# GWC-MCU-002-A_-_Temps.net
KiCad netlist of a schematic drawn in Altium Designer
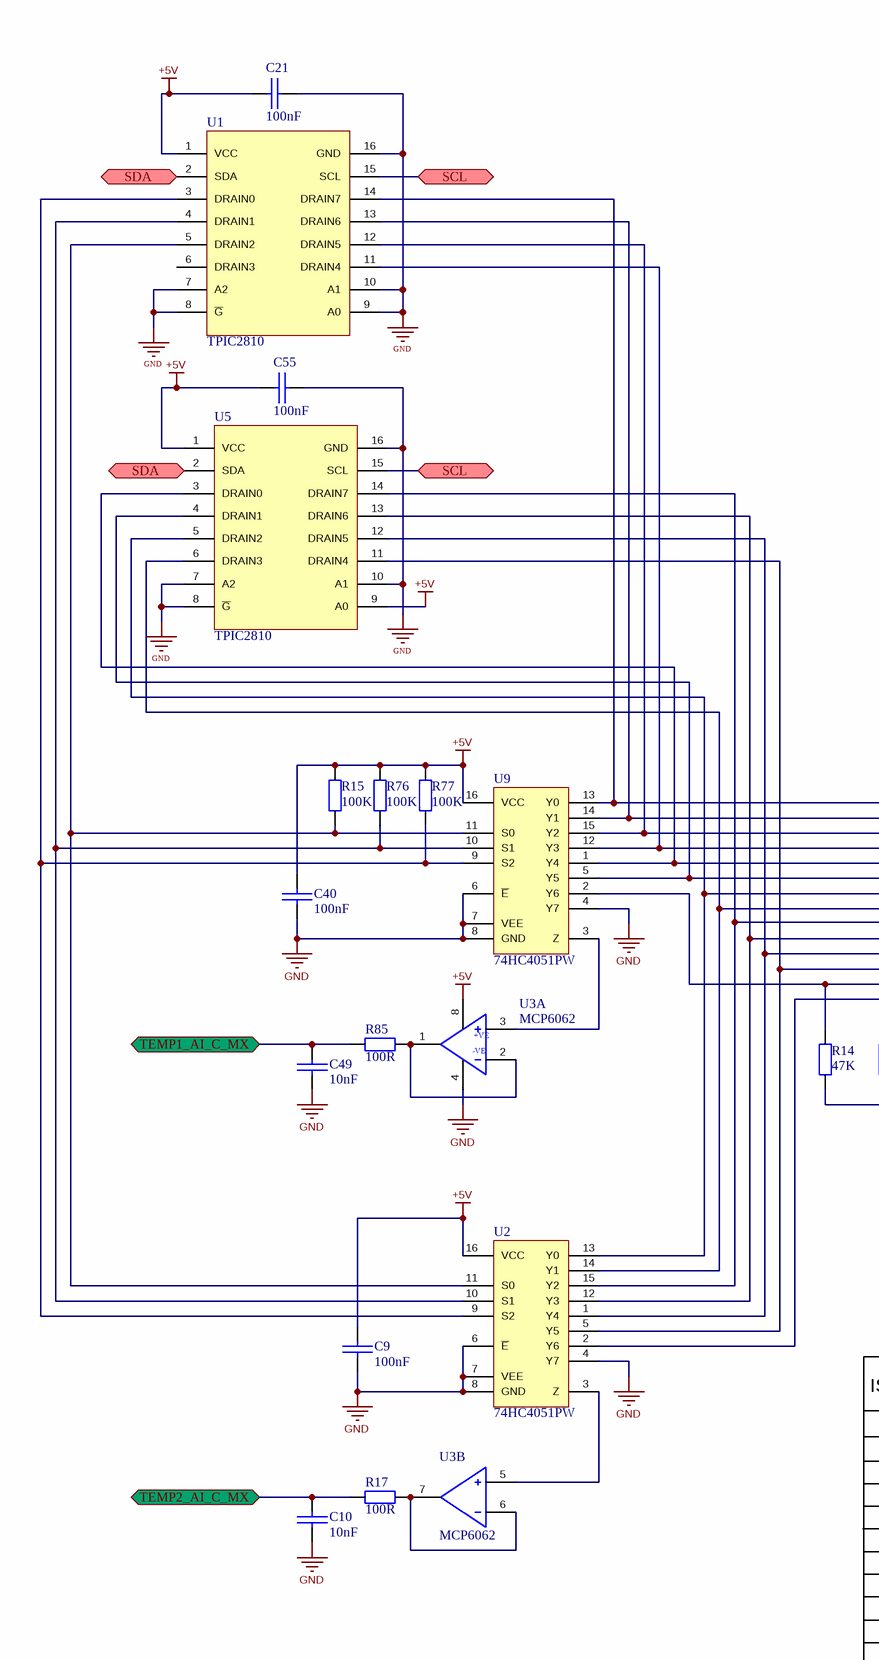
[diagram p0: GWC-MCU-002-A - Temps.SchDoc, left]
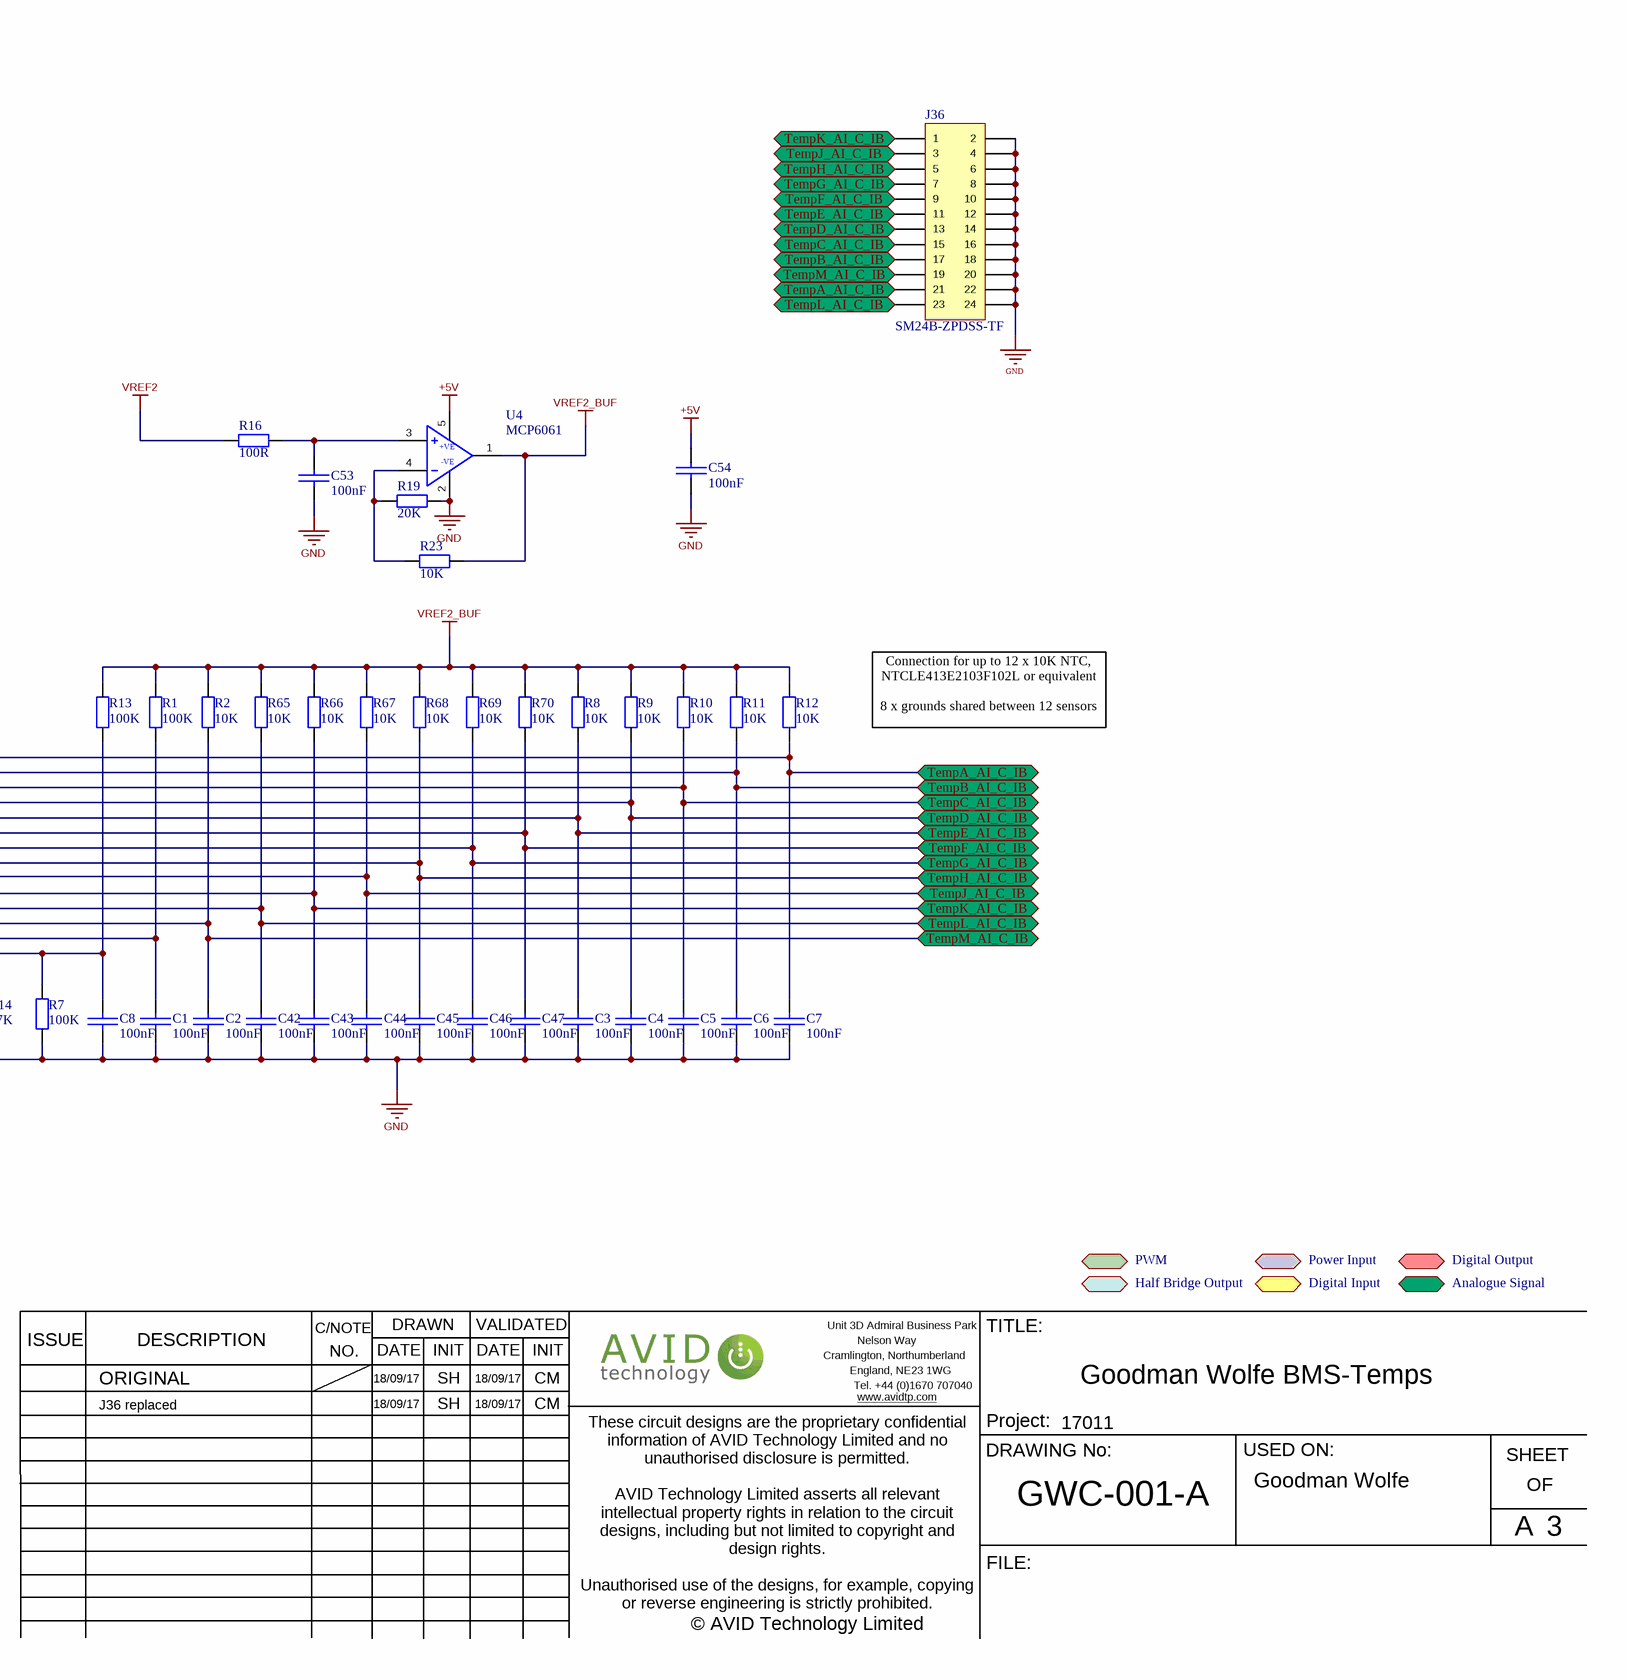
[diagram p1: GWC-MCU-002-A - Temps.SchDoc, right]

(export (version "E")
  (design (tool "Eeschema 10.0.6"))
  (components
    (comp (ref "C1")
      (value "100nF")
      (footprint "C0603")
      (description "100nF 0603 Non Polarised Capacitor")
      (fields (field (name "TOLERANCE") "10%") (field (name "MANUFACTURER") "Kemet"))
      (libsource (lib "Vayon Sch Library") (part "100nF X7R 0603"))
    )
    (comp (ref "C2")
      (value "100nF")
      (footprint "C0603")
      (description "100nF 0603 Non Polarised Capacitor")
      (fields (field (name "TOLERANCE") "10%") (field (name "MANUFACTURER") "Kemet"))
      (libsource (lib "Vayon Sch Library") (part "100nF X7R 0603"))
    )
    (comp (ref "C3")
      (value "100nF")
      (footprint "C0603")
      (description "100nF 0603 Non Polarised Capacitor")
      (fields (field (name "TOLERANCE") "10%") (field (name "MANUFACTURER") "Kemet"))
      (libsource (lib "Vayon Sch Library") (part "100nF X7R 0603"))
    )
    (comp (ref "C4")
      (value "100nF")
      (footprint "C0603")
      (description "100nF 0603 Non Polarised Capacitor")
      (fields (field (name "TOLERANCE") "10%") (field (name "MANUFACTURER") "Kemet"))
      (libsource (lib "Vayon Sch Library") (part "100nF X7R 0603"))
    )
    (comp (ref "C5")
      (value "100nF")
      (footprint "C0603")
      (description "100nF 0603 Non Polarised Capacitor")
      (fields (field (name "TOLERANCE") "10%") (field (name "MANUFACTURER") "Kemet"))
      (libsource (lib "Vayon Sch Library") (part "100nF X7R 0603"))
    )
    (comp (ref "C6")
      (value "100nF")
      (footprint "C0603")
      (description "100nF 0603 Non Polarised Capacitor")
      (fields (field (name "TOLERANCE") "10%") (field (name "MANUFACTURER") "Kemet"))
      (libsource (lib "Vayon Sch Library") (part "100nF X7R 0603"))
    )
    (comp (ref "C7")
      (value "100nF")
      (footprint "C0603")
      (description "100nF 0603 Non Polarised Capacitor")
      (fields (field (name "TOLERANCE") "10%") (field (name "MANUFACTURER") "Kemet"))
      (libsource (lib "Vayon Sch Library") (part "100nF X7R 0603"))
    )
    (comp (ref "C8")
      (value "100nF")
      (footprint "C0603")
      (description "100nF 0603 Non Polarised Capacitor")
      (fields (field (name "TOLERANCE") "10%") (field (name "MANUFACTURER") "Kemet"))
      (libsource (lib "Vayon Sch Library") (part "100nF X7R 0603"))
    )
    (comp (ref "C9")
      (value "100nF")
      (footprint "C0603")
      (description "100nF 0603 Non Polarised Capacitor")
      (fields (field (name "TOLERANCE") "10%") (field (name "MANUFACTURER") "Kemet"))
      (libsource (lib "Vayon Sch Library") (part "100nF X7R 0603"))
    )
    (comp (ref "C10")
      (value "10nF")
      (footprint "0603")
      (description "10nF Non Polarised Capacitor")
      (fields (field (name "TOLERANCE") "10%") (field (name "MANUFACTURER") "Kemet"))
      (libsource (lib "Vayon Sch Library") (part "10nF 0603 X7R"))
    )
    (comp (ref "C21")
      (value "100nF")
      (footprint "C0603")
      (description "100nF 0603 Non Polarised Capacitor")
      (fields (field (name "TOLERANCE") "10%") (field (name "MANUFACTURER") "Kemet"))
      (libsource (lib "Vayon Sch Library") (part "100nF X7R 0603"))
    )
    (comp (ref "C40")
      (value "100nF")
      (footprint "C0603")
      (description "100nF 0603 Non Polarised Capacitor")
      (fields (field (name "TOLERANCE") "10%") (field (name "MANUFACTURER") "Kemet"))
      (libsource (lib "Vayon Sch Library") (part "100nF X7R 0603"))
    )
    (comp (ref "C42")
      (value "100nF")
      (footprint "C0603")
      (description "100nF 0603 Non Polarised Capacitor")
      (fields (field (name "TOLERANCE") "10%") (field (name "MANUFACTURER") "Kemet"))
      (libsource (lib "Vayon Sch Library") (part "100nF X7R 0603"))
    )
    (comp (ref "C43")
      (value "100nF")
      (footprint "C0603")
      (description "100nF 0603 Non Polarised Capacitor")
      (fields (field (name "TOLERANCE") "10%") (field (name "MANUFACTURER") "Kemet"))
      (libsource (lib "Vayon Sch Library") (part "100nF X7R 0603"))
    )
    (comp (ref "C44")
      (value "100nF")
      (footprint "C0603")
      (description "100nF 0603 Non Polarised Capacitor")
      (fields (field (name "TOLERANCE") "10%") (field (name "MANUFACTURER") "Kemet"))
      (libsource (lib "Vayon Sch Library") (part "100nF X7R 0603"))
    )
    (comp (ref "C45")
      (value "100nF")
      (footprint "C0603")
      (description "100nF 0603 Non Polarised Capacitor")
      (fields (field (name "TOLERANCE") "10%") (field (name "MANUFACTURER") "Kemet"))
      (libsource (lib "Vayon Sch Library") (part "100nF X7R 0603"))
    )
    (comp (ref "C46")
      (value "100nF")
      (footprint "C0603")
      (description "100nF 0603 Non Polarised Capacitor")
      (fields (field (name "TOLERANCE") "10%") (field (name "MANUFACTURER") "Kemet"))
      (libsource (lib "Vayon Sch Library") (part "100nF X7R 0603"))
    )
    (comp (ref "C47")
      (value "100nF")
      (footprint "C0603")
      (description "100nF 0603 Non Polarised Capacitor")
      (fields (field (name "TOLERANCE") "10%") (field (name "MANUFACTURER") "Kemet"))
      (libsource (lib "Vayon Sch Library") (part "100nF X7R 0603"))
    )
    (comp (ref "C49")
      (value "10nF")
      (footprint "0603")
      (description "10nF Non Polarised Capacitor")
      (fields (field (name "TOLERANCE") "10%") (field (name "MANUFACTURER") "Kemet"))
      (libsource (lib "Vayon Sch Library") (part "10nF 0603 X7R"))
    )
    (comp (ref "C53")
      (value "100nF")
      (footprint "C0603")
      (description "100nF 0603 Non Polarised Capacitor")
      (fields (field (name "TOLERANCE") "10%") (field (name "MANUFACTURER") "Kemet"))
      (libsource (lib "Vayon Sch Library") (part "100nF X7R 0603"))
    )
    (comp (ref "C54")
      (value "100nF")
      (footprint "C0603")
      (description "100nF 0603 Non Polarised Capacitor")
      (fields (field (name "TOLERANCE") "10%") (field (name "MANUFACTURER") "Kemet"))
      (libsource (lib "Vayon Sch Library") (part "100nF X7R 0603"))
    )
    (comp (ref "C55")
      (value "100nF")
      (footprint "C0603")
      (description "100nF 0603 Non Polarised Capacitor")
      (fields (field (name "TOLERANCE") "10%") (field (name "MANUFACTURER") "Kemet"))
      (libsource (lib "Vayon Sch Library") (part "100nF X7R 0603"))
    )
    (comp (ref "J36")
      (value "SM24B-ZPDSS-TF")
      (footprint "24 Way ZPD Connecctor")
      (description "Header, 24-Pin, Dual row, SM24B-ZPDSS-TF")
      (fields (field (name "PUBLISHER") "Altium Limited"))
      (libsource (lib "Miscellaneous Connectors") (part "Header 12X2"))
    )
    (comp (ref "R1")
      (value "100K")
      (footprint "0603")
      (description "100K 0603 Resistor")
      (fields (field (name "TOLERANCE") "1%") (field (name "MANUFACTURER") "Phycomp"))
      (libsource (lib "Vayon Sch Library") (part "100K 0603 Resistor"))
    )
    (comp (ref "R2")
      (value "10K")
      (footprint "0603")
      (description "10K 0603 Resistor")
      (fields (field (name "TOLERANCE") "1%") (field (name "MANUFACTURER") "Phycomp"))
      (libsource (lib "Vayon Sch Library") (part "10K 0603 Resistor"))
    )
    (comp (ref "R7")
      (value "100K")
      (footprint "0603")
      (description "100K 0603 Resistor")
      (fields (field (name "TOLERANCE") "1%") (field (name "MANUFACTURER") "Phycomp"))
      (libsource (lib "Vayon Sch Library") (part "100K 0603 Resistor"))
    )
    (comp (ref "R8")
      (value "10K")
      (footprint "0603")
      (description "10K 0603 Resistor")
      (fields (field (name "TOLERANCE") "1%") (field (name "MANUFACTURER") "Phycomp"))
      (libsource (lib "Vayon Sch Library") (part "10K 0603 Resistor"))
    )
    (comp (ref "R9")
      (value "10K")
      (footprint "0603")
      (description "10K 0603 Resistor")
      (fields (field (name "TOLERANCE") "1%") (field (name "MANUFACTURER") "Phycomp"))
      (libsource (lib "Vayon Sch Library") (part "10K 0603 Resistor"))
    )
    (comp (ref "R10")
      (value "10K")
      (footprint "0603")
      (description "10K 0603 Resistor")
      (fields (field (name "TOLERANCE") "1%") (field (name "MANUFACTURER") "Phycomp"))
      (libsource (lib "Vayon Sch Library") (part "10K 0603 Resistor"))
    )
    (comp (ref "R11")
      (value "10K")
      (footprint "0603")
      (description "10K 0603 Resistor")
      (fields (field (name "TOLERANCE") "1%") (field (name "MANUFACTURER") "Phycomp"))
      (libsource (lib "Vayon Sch Library") (part "10K 0603 Resistor"))
    )
    (comp (ref "R12")
      (value "10K")
      (footprint "0603")
      (description "10K 0603 Resistor")
      (fields (field (name "TOLERANCE") "1%") (field (name "MANUFACTURER") "Phycomp"))
      (libsource (lib "Vayon Sch Library") (part "10K 0603 Resistor"))
    )
    (comp (ref "R13")
      (value "100K")
      (footprint "0603")
      (description "100K 0603 Resistor")
      (fields (field (name "TOLERANCE") "1%") (field (name "MANUFACTURER") "Phycomp"))
      (libsource (lib "Vayon Sch Library") (part "100K 0603 Resistor"))
    )
    (comp (ref "R14")
      (value "47K")
      (footprint "0603")
      (description "47K 0603 Resistor")
      (fields (field (name "TOLERANCE") "1%") (field (name "MANUFACTURER") "Phycomp"))
      (libsource (lib "Vayon Sch Library") (part "47K 0603 Resistor"))
    )
    (comp (ref "R15")
      (value "100K")
      (footprint "0603")
      (description "100K 0603 Resistor")
      (fields (field (name "TOLERANCE") "1%") (field (name "MANUFACTURER") "Phycomp"))
      (libsource (lib "") (part "100K 0603 Resistor_1"))
    )
    (comp (ref "R16")
      (value "100R")
      (footprint "0603")
      (description "100R 0603 Resistor")
      (fields (field (name "TOLERANCE") "1%") (field (name "MANUFACTURER") "Multicomp"))
      (libsource (lib "Vayon Sch Library") (part "100R 0603 Resistor"))
    )
    (comp (ref "R17")
      (value "100R")
      (footprint "0603")
      (description "100R 0603 Resistor")
      (fields (field (name "TOLERANCE") "1%") (field (name "MANUFACTURER") "Multicomp"))
      (libsource (lib "Vayon Sch Library") (part "100R 0603 Resistor"))
    )
    (comp (ref "R19")
      (value "20K")
      (footprint "0603")
      (description "100R 0603 Resistor")
      (fields (field (name "TOLERANCE") "1%") (field (name "MANUFACTURER") "Multicomp"))
      (libsource (lib "Vayon Sch Library") (part "100R 0603 Resistor"))
    )
    (comp (ref "R23")
      (value "10K")
      (footprint "0603")
      (description "100R 0603 Resistor")
      (fields (field (name "TOLERANCE") "1%") (field (name "MANUFACTURER") "Multicomp"))
      (libsource (lib "Vayon Sch Library") (part "100R 0603 Resistor"))
    )
    (comp (ref "R65")
      (value "10K")
      (footprint "0603")
      (description "10K 0603 Resistor")
      (fields (field (name "TOLERANCE") "1%") (field (name "MANUFACTURER") "Phycomp"))
      (libsource (lib "Vayon Sch Library") (part "10K 0603 Resistor"))
    )
    (comp (ref "R66")
      (value "10K")
      (footprint "0603")
      (description "10K 0603 Resistor")
      (fields (field (name "TOLERANCE") "1%") (field (name "MANUFACTURER") "Phycomp"))
      (libsource (lib "Vayon Sch Library") (part "10K 0603 Resistor"))
    )
    (comp (ref "R67")
      (value "10K")
      (footprint "0603")
      (description "10K 0603 Resistor")
      (fields (field (name "TOLERANCE") "1%") (field (name "MANUFACTURER") "Phycomp"))
      (libsource (lib "Vayon Sch Library") (part "10K 0603 Resistor"))
    )
    (comp (ref "R68")
      (value "10K")
      (footprint "0603")
      (description "10K 0603 Resistor")
      (fields (field (name "TOLERANCE") "1%") (field (name "MANUFACTURER") "Phycomp"))
      (libsource (lib "Vayon Sch Library") (part "10K 0603 Resistor"))
    )
    (comp (ref "R69")
      (value "10K")
      (footprint "0603")
      (description "10K 0603 Resistor")
      (fields (field (name "TOLERANCE") "1%") (field (name "MANUFACTURER") "Phycomp"))
      (libsource (lib "Vayon Sch Library") (part "10K 0603 Resistor"))
    )
    (comp (ref "R70")
      (value "10K")
      (footprint "0603")
      (description "10K 0603 Resistor")
      (fields (field (name "TOLERANCE") "1%") (field (name "MANUFACTURER") "Phycomp"))
      (libsource (lib "Vayon Sch Library") (part "10K 0603 Resistor"))
    )
    (comp (ref "R76")
      (value "100K")
      (footprint "0603")
      (description "100K 0603 Resistor")
      (fields (field (name "TOLERANCE") "1%") (field (name "MANUFACTURER") "Phycomp"))
      (libsource (lib "") (part "100K 0603 Resistor_1"))
    )
    (comp (ref "R77")
      (value "100K")
      (footprint "0603")
      (description "100K 0603 Resistor")
      (fields (field (name "TOLERANCE") "1%") (field (name "MANUFACTURER") "Phycomp"))
      (libsource (lib "Vayon Sch Library") (part "100K 0603 Resistor"))
    )
    (comp (ref "R85")
      (value "100R")
      (footprint "0603")
      (description "100R 0603 Resistor")
      (fields (field (name "TOLERANCE") "1%") (field (name "MANUFACTURER") "Multicomp"))
      (libsource (lib "Vayon Sch Library") (part "100R 0603 Resistor"))
    )
    (comp (ref "U1")
      (value "TPIC2810")
      (footprint "SOIC127P600-TPIC2810")
      (description "TPIC2810D -  Led Driver, 8 Outputs, I2C, 3V-5.5V")
      (fields (field (name "MANUFACTURER") "Texas"))
      (libsource (lib "GWC-MCU-001-A") (part "TPIC2810"))
    )
    (comp (ref "U2")
      (value "74HC4051PW")
      (footprint "TSSOP-16")
      (description "8 Channel Analogue Switch")
      (fields (field (name "MANUFACTURER") "NXP") (field (name "PART NUMBER") "74HC4051PW-Q100,11"))
      (libsource (lib "Vayon Sch Library") (part "74HC4051PW"))
    )
    (comp (ref "U3")
      (value "MCP6062")
      (footprint "SO-8")
      (description "Dual Opamp")
      (fields (field (name "MANUFACTURER") "Microchip") (field (name "PART NUMBER") "MCP6062-E/SN"))
      (libsource (lib "Vayon Sch Library") (part "MCP6062"))
    )
    (comp (ref "U4")
      (value "MCP6061")
      (footprint "SOT-23-5")
      (description "Micropower CMOS Op Amp")
      (fields (field (name "MANUFACTURER") "Microchip") (field (name "PART NUMBER") "MCP6061T-E/OT"))
      (libsource (lib "Vayon Sch Library") (part "MCP6061"))
    )
    (comp (ref "U5")
      (value "TPIC2810")
      (footprint "SOIC127P600-TPIC2810")
      (description "TPIC2810D -  Led Driver, 8 Outputs, I2C, 3V-5.5V")
      (fields (field (name "MANUFACTURER") "Texas"))
      (libsource (lib "GWC-MCU-001-A") (part "TPIC2810"))
    )
    (comp (ref "U9")
      (value "74HC4051PW")
      (footprint "TSSOP-16")
      (description "8 Channel Analogue Switch")
      (fields (field (name "MANUFACTURER") "NXP") (field (name "PART NUMBER") "74HC4051PW-Q100,11"))
      (libsource (lib "Vayon Sch Library") (part "74HC4051PW"))
    )
  )
  (nets
    (net (code "1") (name "+5V") (class "Default")
      (node (ref "C21") (pin "1") (pinfunction "1_1") (pintype "passive"))
      (node (ref "C40") (pin "1") (pinfunction "1_1") (pintype "passive"))
      (node (ref "C54") (pin "1") (pinfunction "1_1") (pintype "passive"))
      (node (ref "C55") (pin "1") (pinfunction "1_1") (pintype "passive"))
      (node (ref "C9") (pin "1") (pinfunction "1_1") (pintype "passive"))
      (node (ref "R15") (pin "1") (pinfunction "1_1") (pintype "passive"))
      (node (ref "R76") (pin "1") (pinfunction "1_1") (pintype "passive"))
      (node (ref "R77") (pin "2") (pinfunction "2_2") (pintype "passive"))
      (node (ref "U1") (pin "1") (pinfunction "VCC_1") (pintype "passive"))
      (node (ref "U2") (pin "16") (pinfunction "VCC_16") (pintype "passive"))
      (node (ref "U3") (pin "8") (pinfunction "+VE_8") (pintype "passive"))
      (node (ref "U4") (pin "5") (pinfunction "+VE_5") (pintype "passive"))
      (node (ref "U5") (pin "1") (pinfunction "VCC_1") (pintype "passive"))
      (node (ref "U5") (pin "9") (pinfunction "A0_9") (pintype "passive"))
      (node (ref "U9") (pin "16") (pinfunction "VCC_16") (pintype "passive"))
    )
    (net (code "3") (name "/SCL") (class "Default")
      (node (ref "U1") (pin "15") (pinfunction "SCL_15") (pintype "passive"))
      (node (ref "U5") (pin "15") (pinfunction "SCL_15") (pintype "passive"))
    )
    (net (code "4") (name "/SDA") (class "Default")
      (node (ref "U1") (pin "2") (pinfunction "SDA_2") (pintype "passive"))
      (node (ref "U5") (pin "2") (pinfunction "SDA_2") (pintype "passive"))
    )
    (net (code "5") (name "/TEMP1_AI_C_MX") (class "Default")
      (node (ref "C49") (pin "1") (pinfunction "1_1") (pintype "passive"))
      (node (ref "R85") (pin "1") (pinfunction "1_1") (pintype "passive"))
    )
    (net (code "6") (name "/TEMP2_AI_C_MX") (class "Default")
      (node (ref "C10") (pin "1") (pinfunction "1_1") (pintype "passive"))
      (node (ref "R17") (pin "1") (pinfunction "1_1") (pintype "passive"))
    )
    (net (code "7") (name "/TempA_AI_C_IB") (class "Default")
      (node (ref "C7") (pin "2") (pinfunction "2_2") (pintype "passive"))
      (node (ref "J36") (pin "21") (pinfunction "21_21") (pintype "passive"))
      (node (ref "R12") (pin "1") (pinfunction "1_1") (pintype "passive"))
      (node (ref "U1") (pin "14") (pinfunction "DRAIN7_14") (pintype "passive"))
      (node (ref "U9") (pin "13") (pinfunction "Y0_13") (pintype "passive"))
    )
    (net (code "8") (name "/TempB_AI_C_IB") (class "Default")
      (node (ref "C6") (pin "2") (pinfunction "2_2") (pintype "passive"))
      (node (ref "J36") (pin "17") (pinfunction "17_17") (pintype "passive"))
      (node (ref "R11") (pin "1") (pinfunction "1_1") (pintype "passive"))
      (node (ref "U1") (pin "13") (pinfunction "DRAIN6_13") (pintype "passive"))
      (node (ref "U9") (pin "14") (pinfunction "Y1_14") (pintype "passive"))
    )
    (net (code "9") (name "/TempC_AI_C_IB") (class "Default")
      (node (ref "C5") (pin "2") (pinfunction "2_2") (pintype "passive"))
      (node (ref "J36") (pin "15") (pinfunction "15_15") (pintype "passive"))
      (node (ref "R10") (pin "1") (pinfunction "1_1") (pintype "passive"))
      (node (ref "U1") (pin "12") (pinfunction "DRAIN5_12") (pintype "passive"))
      (node (ref "U9") (pin "15") (pinfunction "Y2_15") (pintype "passive"))
    )
    (net (code "10") (name "/TempD_AI_C_IB") (class "Default")
      (node (ref "C4") (pin "2") (pinfunction "2_2") (pintype "passive"))
      (node (ref "J36") (pin "13") (pinfunction "13_13") (pintype "passive"))
      (node (ref "R9") (pin "1") (pinfunction "1_1") (pintype "passive"))
      (node (ref "U1") (pin "11") (pinfunction "DRAIN4_11") (pintype "passive"))
      (node (ref "U9") (pin "12") (pinfunction "Y3_12") (pintype "passive"))
    )
    (net (code "11") (name "/TempE_AI_C_IB") (class "Default")
      (node (ref "C3") (pin "2") (pinfunction "2_2") (pintype "passive"))
      (node (ref "J36") (pin "11") (pinfunction "11_11") (pintype "passive"))
      (node (ref "R8") (pin "1") (pinfunction "1_1") (pintype "passive"))
      (node (ref "U5") (pin "3") (pinfunction "DRAIN0_3") (pintype "passive"))
      (node (ref "U9") (pin "1") (pinfunction "Y4_1") (pintype "passive"))
    )
    (net (code "12") (name "/TempF_AI_C_IB") (class "Default")
      (node (ref "C47") (pin "2") (pinfunction "2_2") (pintype "passive"))
      (node (ref "J36") (pin "9") (pinfunction "9_9") (pintype "passive"))
      (node (ref "R70") (pin "1") (pinfunction "1_1") (pintype "passive"))
      (node (ref "U5") (pin "4") (pinfunction "DRAIN1_4") (pintype "passive"))
      (node (ref "U9") (pin "5") (pinfunction "Y5_5") (pintype "passive"))
    )
    (net (code "13") (name "/TempG_AI_C_IB") (class "Default")
      (node (ref "C46") (pin "2") (pinfunction "2_2") (pintype "passive"))
      (node (ref "J36") (pin "7") (pinfunction "7_7") (pintype "passive"))
      (node (ref "R69") (pin "1") (pinfunction "1_1") (pintype "passive"))
      (node (ref "U2") (pin "13") (pinfunction "Y0_13") (pintype "passive"))
      (node (ref "U5") (pin "5") (pinfunction "DRAIN2_5") (pintype "passive"))
    )
    (net (code "14") (name "/TempH_AI_C_IB") (class "Default")
      (node (ref "C45") (pin "2") (pinfunction "2_2") (pintype "passive"))
      (node (ref "J36") (pin "5") (pinfunction "5_5") (pintype "passive"))
      (node (ref "R68") (pin "1") (pinfunction "1_1") (pintype "passive"))
      (node (ref "U2") (pin "14") (pinfunction "Y1_14") (pintype "passive"))
      (node (ref "U5") (pin "6") (pinfunction "DRAIN3_6") (pintype "passive"))
    )
    (net (code "15") (name "/TempJ_AI_C_IB") (class "Default")
      (node (ref "C44") (pin "2") (pinfunction "2_2") (pintype "passive"))
      (node (ref "J36") (pin "3") (pinfunction "3_3") (pintype "passive"))
      (node (ref "R67") (pin "1") (pinfunction "1_1") (pintype "passive"))
      (node (ref "U2") (pin "15") (pinfunction "Y2_15") (pintype "passive"))
      (node (ref "U5") (pin "14") (pinfunction "DRAIN7_14") (pintype "passive"))
    )
    (net (code "16") (name "/TempK_AI_C_IB") (class "Default")
      (node (ref "C43") (pin "2") (pinfunction "2_2") (pintype "passive"))
      (node (ref "J36") (pin "1") (pinfunction "1_1") (pintype "passive"))
      (node (ref "R66") (pin "1") (pinfunction "1_1") (pintype "passive"))
      (node (ref "U2") (pin "12") (pinfunction "Y3_12") (pintype "passive"))
      (node (ref "U5") (pin "13") (pinfunction "DRAIN6_13") (pintype "passive"))
    )
    (net (code "17") (name "/TempL_AI_C_IB") (class "Default")
      (node (ref "C42") (pin "2") (pinfunction "2_2") (pintype "passive"))
      (node (ref "J36") (pin "23") (pinfunction "23_23") (pintype "passive"))
      (node (ref "R65") (pin "1") (pinfunction "1_1") (pintype "passive"))
      (node (ref "U2") (pin "1") (pinfunction "Y4_1") (pintype "passive"))
      (node (ref "U5") (pin "12") (pinfunction "DRAIN5_12") (pintype "passive"))
    )
    (net (code "18") (name "/TempM_AI_C_IB") (class "Default")
      (node (ref "C2") (pin "2") (pinfunction "2_2") (pintype "passive"))
      (node (ref "J36") (pin "19") (pinfunction "19_19") (pintype "passive"))
      (node (ref "R2") (pin "1") (pinfunction "1_1") (pintype "passive"))
      (node (ref "U2") (pin "5") (pinfunction "Y5_5") (pintype "passive"))
      (node (ref "U5") (pin "11") (pinfunction "DRAIN4_11") (pintype "passive"))
    )
    (net (code "19") (name "GND") (class "Default")
      (node (ref "C1") (pin "1") (pinfunction "1_1") (pintype "passive"))
      (node (ref "C10") (pin "2") (pinfunction "2_2") (pintype "passive"))
      (node (ref "C2") (pin "1") (pinfunction "1_1") (pintype "passive"))
      (node (ref "C21") (pin "2") (pinfunction "2_2") (pintype "passive"))
      (node (ref "C3") (pin "1") (pinfunction "1_1") (pintype "passive"))
      (node (ref "C4") (pin "1") (pinfunction "1_1") (pintype "passive"))
      (node (ref "C40") (pin "2") (pinfunction "2_2") (pintype "passive"))
      (node (ref "C42") (pin "1") (pinfunction "1_1") (pintype "passive"))
      (node (ref "C43") (pin "1") (pinfunction "1_1") (pintype "passive"))
      (node (ref "C44") (pin "1") (pinfunction "1_1") (pintype "passive"))
      (node (ref "C45") (pin "1") (pinfunction "1_1") (pintype "passive"))
      (node (ref "C46") (pin "1") (pinfunction "1_1") (pintype "passive"))
      (node (ref "C47") (pin "1") (pinfunction "1_1") (pintype "passive"))
      (node (ref "C49") (pin "2") (pinfunction "2_2") (pintype "passive"))
      (node (ref "C5") (pin "1") (pinfunction "1_1") (pintype "passive"))
      (node (ref "C53") (pin "2") (pinfunction "2_2") (pintype "passive"))
      (node (ref "C54") (pin "2") (pinfunction "2_2") (pintype "passive"))
      (node (ref "C55") (pin "2") (pinfunction "2_2") (pintype "passive"))
      (node (ref "C6") (pin "1") (pinfunction "1_1") (pintype "passive"))
      (node (ref "C7") (pin "1") (pinfunction "1_1") (pintype "passive"))
      (node (ref "C8") (pin "1") (pinfunction "1_1") (pintype "passive"))
      (node (ref "C9") (pin "2") (pinfunction "2_2") (pintype "passive"))
      (node (ref "J36") (pin "10") (pinfunction "10_10") (pintype "passive"))
      (node (ref "J36") (pin "12") (pinfunction "12_12") (pintype "passive"))
      (node (ref "J36") (pin "14") (pinfunction "14_14") (pintype "passive"))
      (node (ref "J36") (pin "16") (pinfunction "16_16") (pintype "passive"))
      (node (ref "J36") (pin "18") (pinfunction "18_18") (pintype "passive"))
      (node (ref "J36") (pin "2") (pinfunction "2_2") (pintype "passive"))
      (node (ref "J36") (pin "20") (pinfunction "20_20") (pintype "passive"))
      (node (ref "J36") (pin "22") (pinfunction "22_22") (pintype "passive"))
      (node (ref "J36") (pin "24") (pinfunction "24_24") (pintype "passive"))
      (node (ref "J36") (pin "4") (pinfunction "4_4") (pintype "passive"))
      (node (ref "J36") (pin "6") (pinfunction "6_6") (pintype "passive"))
      (node (ref "J36") (pin "8") (pinfunction "8_8") (pintype "passive"))
      (node (ref "R14") (pin "1") (pinfunction "1_1") (pintype "passive"))
      (node (ref "R19") (pin "2") (pinfunction "2_2") (pintype "passive"))
      (node (ref "R7") (pin "1") (pinfunction "1_1") (pintype "passive"))
      (node (ref "U1") (pin "10") (pinfunction "A1_10") (pintype "passive"))
      (node (ref "U1") (pin "16") (pinfunction "GND_16") (pintype "passive"))
      (node (ref "U1") (pin "7") (pinfunction "A2_7") (pintype "passive"))
      (node (ref "U1") (pin "8") (pinfunction "~{G}_8") (pintype "passive"))
      (node (ref "U1") (pin "9") (pinfunction "A0_9") (pintype "passive"))
      (node (ref "U2") (pin "4") (pinfunction "Y7_4") (pintype "passive"))
      (node (ref "U2") (pin "6") (pinfunction "~{E}_6") (pintype "passive"))
      (node (ref "U2") (pin "7") (pinfunction "VEE_7") (pintype "passive"))
      (node (ref "U2") (pin "8") (pinfunction "GND_8") (pintype "passive"))
      (node (ref "U3") (pin "4") (pinfunction "-VE_4") (pintype "passive"))
      (node (ref "U4") (pin "2") (pinfunction "-VE_2") (pintype "passive"))
      (node (ref "U5") (pin "10") (pinfunction "A1_10") (pintype "passive"))
      (node (ref "U5") (pin "16") (pinfunction "GND_16") (pintype "passive"))
      (node (ref "U5") (pin "7") (pinfunction "A2_7") (pintype "passive"))
      (node (ref "U5") (pin "8") (pinfunction "~{G}_8") (pintype "passive"))
      (node (ref "U9") (pin "4") (pinfunction "Y7_4") (pintype "passive"))
      (node (ref "U9") (pin "6") (pinfunction "~{E}_6") (pintype "passive"))
      (node (ref "U9") (pin "7") (pinfunction "VEE_7") (pintype "passive"))
      (node (ref "U9") (pin "8") (pinfunction "GND_8") (pintype "passive"))
    )
    (net (code "20") (name "Net-(U1-DRAIN0)") (class "Default")
      (node (ref "R77") (pin "1") (pinfunction "1_1") (pintype "passive"))
      (node (ref "U1") (pin "3") (pinfunction "DRAIN0_3") (pintype "passive"))
      (node (ref "U2") (pin "9") (pinfunction "S2_9") (pintype "passive"))
      (node (ref "U9") (pin "9") (pinfunction "S2_9") (pintype "passive"))
    )
    (net (code "21") (name "Net-(U1-DRAIN1)") (class "Default")
      (node (ref "R76") (pin "2") (pinfunction "2_2") (pintype "passive"))
      (node (ref "U1") (pin "4") (pinfunction "DRAIN1_4") (pintype "passive"))
      (node (ref "U2") (pin "10") (pinfunction "S1_10") (pintype "passive"))
      (node (ref "U9") (pin "10") (pinfunction "S1_10") (pintype "passive"))
    )
    (net (code "22") (name "Net-(U1-DRAIN2)") (class "Default")
      (node (ref "R15") (pin "2") (pinfunction "2_2") (pintype "passive"))
      (node (ref "U1") (pin "5") (pinfunction "DRAIN2_5") (pintype "passive"))
      (node (ref "U2") (pin "11") (pinfunction "S0_11") (pintype "passive"))
      (node (ref "U9") (pin "11") (pinfunction "S0_11") (pintype "passive"))
    )
    (net (code "23") (name "Net-(U2-Y6)") (class "Default")
      (node (ref "C8") (pin "2") (pinfunction "2_2") (pintype "passive"))
      (node (ref "R13") (pin "1") (pinfunction "1_1") (pintype "passive"))
      (node (ref "R7") (pin "2") (pinfunction "2_2") (pintype "passive"))
      (node (ref "U2") (pin "2") (pinfunction "Y6_2") (pintype "passive"))
    )
    (net (code "24") (name "Net-(U2-Z)") (class "Default")
      (node (ref "U2") (pin "3") (pinfunction "Z_3") (pintype "passive"))
      (node (ref "U3") (pin "5") (pinfunction "IN2_+_5") (pintype "passive"))
    )
    (net (code "25") (name "Net-(U3A-IN1_+)") (class "Default")
      (node (ref "U3") (pin "3") (pinfunction "IN1_+_3") (pintype "passive"))
      (node (ref "U9") (pin "3") (pinfunction "Z_3") (pintype "passive"))
    )
    (net (code "26") (name "Net-(U3A-IN1_-)") (class "Default")
      (node (ref "R85") (pin "2") (pinfunction "2_2") (pintype "passive"))
      (node (ref "U3") (pin "1") (pinfunction "OUT1_1") (pintype "passive"))
      (node (ref "U3") (pin "2") (pinfunction "IN1_-_2") (pintype "passive"))
    )
    (net (code "27") (name "Net-(U3B-IN2_-)") (class "Default")
      (node (ref "R17") (pin "2") (pinfunction "2_2") (pintype "passive"))
      (node (ref "U3") (pin "6") (pinfunction "IN2_-_6") (pintype "passive"))
      (node (ref "U3") (pin "7") (pinfunction "OUT2_7") (pintype "passive"))
    )
    (net (code "28") (name "Net-(U4-IN1_+)") (class "Default")
      (node (ref "C53") (pin "1") (pinfunction "1_1") (pintype "passive"))
      (node (ref "R16") (pin "2") (pinfunction "2_2") (pintype "passive"))
      (node (ref "U4") (pin "3") (pinfunction "IN1_+_3") (pintype "passive"))
    )
    (net (code "29") (name "Net-(U4-IN1_-)") (class "Default")
      (node (ref "R19") (pin "1") (pinfunction "1_1") (pintype "passive"))
      (node (ref "R23") (pin "1") (pinfunction "1_1") (pintype "passive"))
      (node (ref "U4") (pin "4") (pinfunction "IN1_-_4") (pintype "passive"))
    )
    (net (code "30") (name "Net-(U9-Y6)") (class "Default")
      (node (ref "C1") (pin "2") (pinfunction "2_2") (pintype "passive"))
      (node (ref "R1") (pin "1") (pinfunction "1_1") (pintype "passive"))
      (node (ref "R14") (pin "2") (pinfunction "2_2") (pintype "passive"))
      (node (ref "U9") (pin "2") (pinfunction "Y6_2") (pintype "passive"))
    )
    (net (code "31") (name "VREF2") (class "Default")
      (node (ref "R16") (pin "1") (pinfunction "1_1") (pintype "passive"))
    )
    (net (code "32") (name "VREF2_BUF") (class "Default")
      (node (ref "R1") (pin "2") (pinfunction "2_2") (pintype "passive"))
      (node (ref "R10") (pin "2") (pinfunction "2_2") (pintype "passive"))
      (node (ref "R11") (pin "2") (pinfunction "2_2") (pintype "passive"))
      (node (ref "R12") (pin "2") (pinfunction "2_2") (pintype "passive"))
      (node (ref "R13") (pin "2") (pinfunction "2_2") (pintype "passive"))
      (node (ref "R2") (pin "2") (pinfunction "2_2") (pintype "passive"))
      (node (ref "R23") (pin "2") (pinfunction "2_2") (pintype "passive"))
      (node (ref "R65") (pin "2") (pinfunction "2_2") (pintype "passive"))
      (node (ref "R66") (pin "2") (pinfunction "2_2") (pintype "passive"))
      (node (ref "R67") (pin "2") (pinfunction "2_2") (pintype "passive"))
      (node (ref "R68") (pin "2") (pinfunction "2_2") (pintype "passive"))
      (node (ref "R69") (pin "2") (pinfunction "2_2") (pintype "passive"))
      (node (ref "R70") (pin "2") (pinfunction "2_2") (pintype "passive"))
      (node (ref "R8") (pin "2") (pinfunction "2_2") (pintype "passive"))
      (node (ref "R9") (pin "2") (pinfunction "2_2") (pintype "passive"))
      (node (ref "U4") (pin "1") (pinfunction "OUT1_1") (pintype "passive"))
    )
    (net (code "33") (name "unconnected-(U1-DRAIN3-Pad6)") (class "Default")
      (node (ref "U1") (pin "6") (pinfunction "DRAIN3_6") (pintype "passive"))
    )
  )
)
